# Multivibrator.net
KiCad netlist of a schematic drawn in Altium Designer
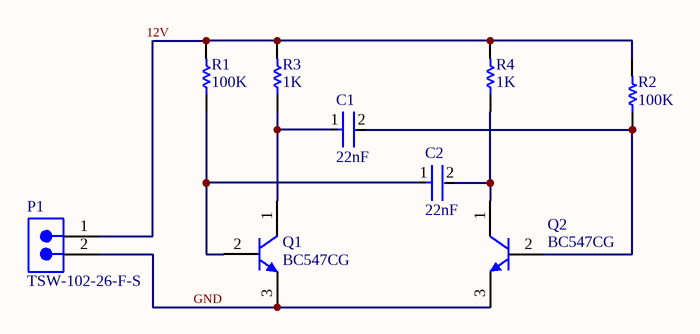
[diagram p0: Multivibrator.SchDoc]

(export (version "E")
  (design (tool "Eeschema 10.0.6"))
  (components
    (comp (ref "C1")
      (value "22nF")
      (footprint "FP-C0603C-CF-MFG")
      (description "CAP CER 0.022UF 16V 5% X7R 0603")
      (fields
        (field (name "TOLERANCE") "0.05")
        (field (name "OCTOPART") "https://octopart.com/c0603c223j4ractu-kemet-12542861")
      )
      (libsource (lib "Altium Content Vault") (part "b4654b650e69147ec39a6b967a45e02"))
    )
    (comp (ref "C2")
      (value "22nF")
      (footprint "FP-C0603C-CF-MFG")
      (description "CAP CER 0.022UF 16V 5% X7R 0603")
      (fields
        (field (name "TOLERANCE") "0.05")
        (field (name "OCTOPART") "https://octopart.com/c0603c223j4ractu-kemet-12542861")
      )
      (libsource (lib "Altium Content Vault") (part "b4654b650e69147ec39a6b967a45e02"))
    )
    (comp (ref "P1")
      (value "TSW-102-26-F-S")
      (footprint "SMTC-TSW-102-26-XX-S")
      (description "0.025\" SQ Post Header, Through-hole, Vertical, -55 to 125 degC, 2.54 mm Pitch, 2-Pin, Male, RoHS")
      (fields (field (name "MANUFACTURER") "Samtec"))
      (libsource (lib "Altium Content Vault") (part "SMTC-TSW-102-X-X-S-X"))
    )
    (comp (ref "Q1")
      (value "BC547CG")
      (footprint "ONSC-TO-92-3-29-11")
      (description "Amplifier Transistor, NPN Silicon, 3-Pin TO-92, Pb-Free, Bulk Box")
      (fields (field (name "MANUFACTURER") "On Semiconductor"))
      (libsource (lib "Altium Content Vault") (part "ONSC-NPN-C1B2E3-3"))
    )
    (comp (ref "Q2")
      (value "BC547CG")
      (footprint "ONSC-TO-92-3-29-11")
      (description "Amplifier Transistor, NPN Silicon, 3-Pin TO-92, Pb-Free, Bulk Box")
      (fields (field (name "MANUFACTURER") "On Semiconductor"))
      (libsource (lib "Altium Content Vault") (part "ONSC-NPN-C1B2E3-3"))
    )
    (comp (ref "R1")
      (value "100K")
      (footprint "RESC2013X70X40NL20T20")
      (fields (field (name "PART NUMBER") "ERJ-6GEYJ104V") (field (name "MANUFACTURER") "Panasonic"))
      (libsource (lib "Altium Content Vault") (part "RES"))
    )
    (comp (ref "R2")
      (value "100K")
      (footprint "RESC2013X70X40NL20T20")
      (fields (field (name "PART NUMBER") "ERJ-6GEYJ104V") (field (name "MANUFACTURER") "Panasonic"))
      (libsource (lib "Altium Content Vault") (part "RES"))
    )
    (comp (ref "R3")
      (value "1K")
      (footprint "RESC2013X70X40LL20T20")
      (fields (field (name "MANUFACTURER") "Panasonic") (field (name "PART NUMBER") "ERJ-P06J102V"))
      (libsource (lib "Altium Content Vault") (part "RES"))
    )
    (comp (ref "R4")
      (value "1K")
      (footprint "RESC2013X70X40LL20T20")
      (fields (field (name "MANUFACTURER") "Panasonic") (field (name "PART NUMBER") "ERJ-P06J102V"))
      (libsource (lib "Altium Content Vault") (part "RES"))
    )
  )
  (nets
    (net (code "1") (name "/12V") (class "Default")
      (node (ref "P1") (pin "1") (pinfunction "1_1") (pintype "passive"))
      (node (ref "R1") (pin "2") (pinfunction "2_2") (pintype "passive"))
      (node (ref "R2") (pin "2") (pinfunction "2_2") (pintype "passive"))
      (node (ref "R3") (pin "2") (pinfunction "2_2") (pintype "passive"))
      (node (ref "R4") (pin "2") (pinfunction "2_2") (pintype "passive"))
    )
    (net (code "2") (name "/GND") (class "Default")
      (node (ref "P1") (pin "2") (pinfunction "2_2") (pintype "passive"))
      (node (ref "Q1") (pin "3") (pinfunction "E_3") (pintype "passive"))
      (node (ref "Q2") (pin "3") (pinfunction "E_3") (pintype "passive"))
    )
    (net (code "3") (name "Net-(Q1-B)") (class "Default")
      (node (ref "C2") (pin "1") (pinfunction "1_1") (pintype "passive"))
      (node (ref "Q1") (pin "2") (pinfunction "B_2") (pintype "passive"))
      (node (ref "R1") (pin "1") (pinfunction "1_1") (pintype "passive"))
    )
    (net (code "4") (name "Net-(Q1-C)") (class "Default")
      (node (ref "C1") (pin "1") (pinfunction "1_1") (pintype "passive"))
      (node (ref "Q1") (pin "1") (pinfunction "C_1") (pintype "passive"))
      (node (ref "R3") (pin "1") (pinfunction "1_1") (pintype "passive"))
    )
    (net (code "5") (name "Net-(Q2-B)") (class "Default")
      (node (ref "C1") (pin "2") (pinfunction "2_2") (pintype "passive"))
      (node (ref "Q2") (pin "2") (pinfunction "B_2") (pintype "passive"))
      (node (ref "R2") (pin "1") (pinfunction "1_1") (pintype "passive"))
    )
    (net (code "6") (name "Net-(Q2-C)") (class "Default")
      (node (ref "C2") (pin "2") (pinfunction "2_2") (pintype "passive"))
      (node (ref "Q2") (pin "1") (pinfunction "C_1") (pintype "passive"))
      (node (ref "R4") (pin "1") (pinfunction "1_1") (pintype "passive"))
    )
  )
)
